# input1.net
KiCad netlist of a schematic drawn in Altium Designer
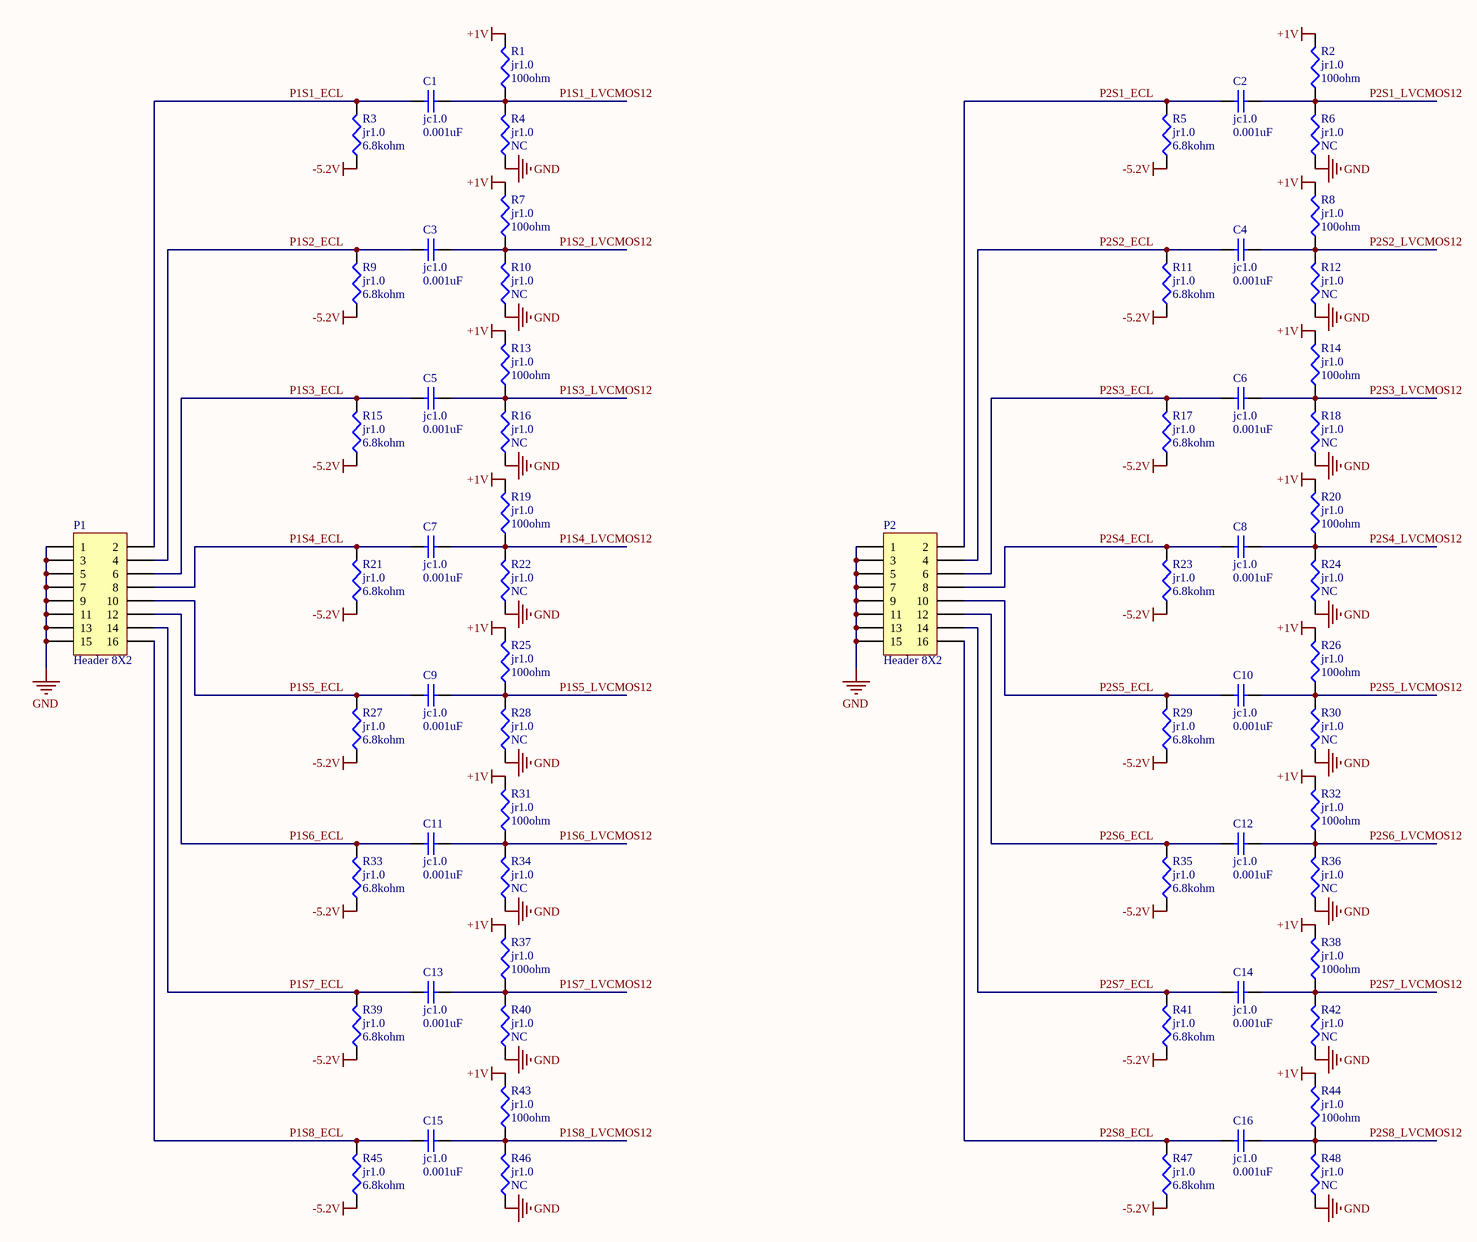
[diagram p0: input1.SchDoc]

(export (version "E")
  (design (tool "Eeschema 10.0.6"))
  (components
    (comp (ref "C1")
      (value "jc1.0")
      (footprint "0402")
      (description "Capacitor")
      (fields (field (name "ALTIUM_VALUE") "0.001uF") (field (name "PUBLISHER") "Altium Limited"))
      (libsource (lib "LIB01DXP2006SchLib") (part "Cap"))
    )
    (comp (ref "C2")
      (value "jc1.0")
      (footprint "0402")
      (description "Capacitor")
      (fields (field (name "ALTIUM_VALUE") "0.001uF") (field (name "PUBLISHER") "Altium Limited"))
      (libsource (lib "LIB01DXP2006SchLib") (part "Cap"))
    )
    (comp (ref "C3")
      (value "jc1.0")
      (footprint "0402")
      (description "Capacitor")
      (fields (field (name "ALTIUM_VALUE") "0.001uF") (field (name "PUBLISHER") "Altium Limited"))
      (libsource (lib "LIB01DXP2006SchLib") (part "Cap"))
    )
    (comp (ref "C4")
      (value "jc1.0")
      (footprint "0402")
      (description "Capacitor")
      (fields (field (name "ALTIUM_VALUE") "0.001uF") (field (name "PUBLISHER") "Altium Limited"))
      (libsource (lib "LIB01DXP2006SchLib") (part "Cap"))
    )
    (comp (ref "C5")
      (value "jc1.0")
      (footprint "0402")
      (description "Capacitor")
      (fields (field (name "ALTIUM_VALUE") "0.001uF") (field (name "PUBLISHER") "Altium Limited"))
      (libsource (lib "LIB01DXP2006SchLib") (part "Cap"))
    )
    (comp (ref "C6")
      (value "jc1.0")
      (footprint "0402")
      (description "Capacitor")
      (fields (field (name "ALTIUM_VALUE") "0.001uF") (field (name "PUBLISHER") "Altium Limited"))
      (libsource (lib "LIB01DXP2006SchLib") (part "Cap"))
    )
    (comp (ref "C7")
      (value "jc1.0")
      (footprint "0402")
      (description "Capacitor")
      (fields (field (name "ALTIUM_VALUE") "0.001uF") (field (name "PUBLISHER") "Altium Limited"))
      (libsource (lib "LIB01DXP2006SchLib") (part "Cap"))
    )
    (comp (ref "C8")
      (value "jc1.0")
      (footprint "0402")
      (description "Capacitor")
      (fields (field (name "ALTIUM_VALUE") "0.001uF") (field (name "PUBLISHER") "Altium Limited"))
      (libsource (lib "LIB01DXP2006SchLib") (part "Cap"))
    )
    (comp (ref "C9")
      (value "jc1.0")
      (footprint "0402")
      (description "Capacitor")
      (fields (field (name "ALTIUM_VALUE") "0.001uF") (field (name "PUBLISHER") "Altium Limited"))
      (libsource (lib "LIB01DXP2006SchLib") (part "Cap"))
    )
    (comp (ref "C10")
      (value "jc1.0")
      (footprint "0402")
      (description "Capacitor")
      (fields (field (name "ALTIUM_VALUE") "0.001uF") (field (name "PUBLISHER") "Altium Limited"))
      (libsource (lib "LIB01DXP2006SchLib") (part "Cap"))
    )
    (comp (ref "C11")
      (value "jc1.0")
      (footprint "0402")
      (description "Capacitor")
      (fields (field (name "ALTIUM_VALUE") "0.001uF") (field (name "PUBLISHER") "Altium Limited"))
      (libsource (lib "LIB01DXP2006SchLib") (part "Cap"))
    )
    (comp (ref "C12")
      (value "jc1.0")
      (footprint "0402")
      (description "Capacitor")
      (fields (field (name "ALTIUM_VALUE") "0.001uF") (field (name "PUBLISHER") "Altium Limited"))
      (libsource (lib "LIB01DXP2006SchLib") (part "Cap"))
    )
    (comp (ref "C13")
      (value "jc1.0")
      (footprint "0402")
      (description "Capacitor")
      (fields (field (name "ALTIUM_VALUE") "0.001uF") (field (name "PUBLISHER") "Altium Limited"))
      (libsource (lib "LIB01DXP2006SchLib") (part "Cap"))
    )
    (comp (ref "C14")
      (value "jc1.0")
      (footprint "0402")
      (description "Capacitor")
      (fields (field (name "ALTIUM_VALUE") "0.001uF") (field (name "PUBLISHER") "Altium Limited"))
      (libsource (lib "LIB01DXP2006SchLib") (part "Cap"))
    )
    (comp (ref "C15")
      (value "jc1.0")
      (footprint "0402")
      (description "Capacitor")
      (fields (field (name "ALTIUM_VALUE") "0.001uF") (field (name "PUBLISHER") "Altium Limited"))
      (libsource (lib "LIB01DXP2006SchLib") (part "Cap"))
    )
    (comp (ref "C16")
      (value "jc1.0")
      (footprint "0402")
      (description "Capacitor")
      (fields (field (name "ALTIUM_VALUE") "0.001uF") (field (name "PUBLISHER") "Altium Limited"))
      (libsource (lib "LIB01DXP2006SchLib") (part "Cap"))
    )
    (comp (ref "P1")
      (value "Header 8X2")
      (footprint "HDR2X8")
      (description "Header, 8-Pin, Dual row")
      (fields (field (name "PUBLISHER") "Altium Limited"))
      (libsource (lib "Miscellaneous Connectors") (part "Header 8X2"))
    )
    (comp (ref "P2")
      (value "Header 8X2")
      (footprint "HDR2X8")
      (description "Header, 8-Pin, Dual row")
      (fields (field (name "PUBLISHER") "Altium Limited"))
      (libsource (lib "Miscellaneous Connectors") (part "Header 8X2"))
    )
    (comp (ref "R1")
      (value "jr1.0")
      (footprint "0402")
      (description "Resistor")
      (fields (field (name "ALTIUM_VALUE") "100ohm") (field (name "PUBLISHER") "Altium Limited"))
      (libsource (lib "LIB01DXP2006SchLib") (part "Res"))
    )
    (comp (ref "R2")
      (value "jr1.0")
      (footprint "0402")
      (description "Resistor")
      (fields (field (name "ALTIUM_VALUE") "100ohm") (field (name "PUBLISHER") "Altium Limited"))
      (libsource (lib "LIB01DXP2006SchLib") (part "Res"))
    )
    (comp (ref "R3")
      (value "jr1.0")
      (footprint "0402")
      (description "Resistor")
      (fields (field (name "ALTIUM_VALUE") "6.8kohm") (field (name "PUBLISHER") "Altium Limited"))
      (libsource (lib "LIB01DXP2006SchLib") (part "Res"))
    )
    (comp (ref "R4")
      (value "jr1.0")
      (footprint "0402")
      (description "Resistor")
      (fields (field (name "ALTIUM_VALUE") "NC") (field (name "PUBLISHER") "Altium Limited"))
      (libsource (lib "LIB01DXP2006SchLib") (part "Res"))
    )
    (comp (ref "R5")
      (value "jr1.0")
      (footprint "0402")
      (description "Resistor")
      (fields (field (name "ALTIUM_VALUE") "6.8kohm") (field (name "PUBLISHER") "Altium Limited"))
      (libsource (lib "LIB01DXP2006SchLib") (part "Res"))
    )
    (comp (ref "R6")
      (value "jr1.0")
      (footprint "0402")
      (description "Resistor")
      (fields (field (name "ALTIUM_VALUE") "NC") (field (name "PUBLISHER") "Altium Limited"))
      (libsource (lib "LIB01DXP2006SchLib") (part "Res"))
    )
    (comp (ref "R7")
      (value "jr1.0")
      (footprint "0402")
      (description "Resistor")
      (fields (field (name "ALTIUM_VALUE") "100ohm") (field (name "PUBLISHER") "Altium Limited"))
      (libsource (lib "LIB01DXP2006SchLib") (part "Res"))
    )
    (comp (ref "R8")
      (value "jr1.0")
      (footprint "0402")
      (description "Resistor")
      (fields (field (name "ALTIUM_VALUE") "100ohm") (field (name "PUBLISHER") "Altium Limited"))
      (libsource (lib "LIB01DXP2006SchLib") (part "Res"))
    )
    (comp (ref "R9")
      (value "jr1.0")
      (footprint "0402")
      (description "Resistor")
      (fields (field (name "ALTIUM_VALUE") "6.8kohm") (field (name "PUBLISHER") "Altium Limited"))
      (libsource (lib "LIB01DXP2006SchLib") (part "Res"))
    )
    (comp (ref "R10")
      (value "jr1.0")
      (footprint "0402")
      (description "Resistor")
      (fields (field (name "ALTIUM_VALUE") "NC") (field (name "PUBLISHER") "Altium Limited"))
      (libsource (lib "LIB01DXP2006SchLib") (part "Res"))
    )
    (comp (ref "R11")
      (value "jr1.0")
      (footprint "0402")
      (description "Resistor")
      (fields (field (name "ALTIUM_VALUE") "6.8kohm") (field (name "PUBLISHER") "Altium Limited"))
      (libsource (lib "LIB01DXP2006SchLib") (part "Res"))
    )
    (comp (ref "R12")
      (value "jr1.0")
      (footprint "0402")
      (description "Resistor")
      (fields (field (name "ALTIUM_VALUE") "NC") (field (name "PUBLISHER") "Altium Limited"))
      (libsource (lib "LIB01DXP2006SchLib") (part "Res"))
    )
    (comp (ref "R13")
      (value "jr1.0")
      (footprint "0402")
      (description "Resistor")
      (fields (field (name "ALTIUM_VALUE") "100ohm") (field (name "PUBLISHER") "Altium Limited"))
      (libsource (lib "LIB01DXP2006SchLib") (part "Res"))
    )
    (comp (ref "R14")
      (value "jr1.0")
      (footprint "0402")
      (description "Resistor")
      (fields (field (name "ALTIUM_VALUE") "100ohm") (field (name "PUBLISHER") "Altium Limited"))
      (libsource (lib "LIB01DXP2006SchLib") (part "Res"))
    )
    (comp (ref "R15")
      (value "jr1.0")
      (footprint "0402")
      (description "Resistor")
      (fields (field (name "ALTIUM_VALUE") "6.8kohm") (field (name "PUBLISHER") "Altium Limited"))
      (libsource (lib "LIB01DXP2006SchLib") (part "Res"))
    )
    (comp (ref "R16")
      (value "jr1.0")
      (footprint "0402")
      (description "Resistor")
      (fields (field (name "ALTIUM_VALUE") "NC") (field (name "PUBLISHER") "Altium Limited"))
      (libsource (lib "LIB01DXP2006SchLib") (part "Res"))
    )
    (comp (ref "R17")
      (value "jr1.0")
      (footprint "0402")
      (description "Resistor")
      (fields (field (name "ALTIUM_VALUE") "6.8kohm") (field (name "PUBLISHER") "Altium Limited"))
      (libsource (lib "LIB01DXP2006SchLib") (part "Res"))
    )
    (comp (ref "R18")
      (value "jr1.0")
      (footprint "0402")
      (description "Resistor")
      (fields (field (name "ALTIUM_VALUE") "NC") (field (name "PUBLISHER") "Altium Limited"))
      (libsource (lib "LIB01DXP2006SchLib") (part "Res"))
    )
    (comp (ref "R19")
      (value "jr1.0")
      (footprint "0402")
      (description "Resistor")
      (fields (field (name "ALTIUM_VALUE") "100ohm") (field (name "PUBLISHER") "Altium Limited"))
      (libsource (lib "LIB01DXP2006SchLib") (part "Res"))
    )
    (comp (ref "R20")
      (value "jr1.0")
      (footprint "0402")
      (description "Resistor")
      (fields (field (name "ALTIUM_VALUE") "100ohm") (field (name "PUBLISHER") "Altium Limited"))
      (libsource (lib "LIB01DXP2006SchLib") (part "Res"))
    )
    (comp (ref "R21")
      (value "jr1.0")
      (footprint "0402")
      (description "Resistor")
      (fields (field (name "ALTIUM_VALUE") "6.8kohm") (field (name "PUBLISHER") "Altium Limited"))
      (libsource (lib "LIB01DXP2006SchLib") (part "Res"))
    )
    (comp (ref "R22")
      (value "jr1.0")
      (footprint "0402")
      (description "Resistor")
      (fields (field (name "ALTIUM_VALUE") "NC") (field (name "PUBLISHER") "Altium Limited"))
      (libsource (lib "LIB01DXP2006SchLib") (part "Res"))
    )
    (comp (ref "R23")
      (value "jr1.0")
      (footprint "0402")
      (description "Resistor")
      (fields (field (name "ALTIUM_VALUE") "6.8kohm") (field (name "PUBLISHER") "Altium Limited"))
      (libsource (lib "LIB01DXP2006SchLib") (part "Res"))
    )
    (comp (ref "R24")
      (value "jr1.0")
      (footprint "0402")
      (description "Resistor")
      (fields (field (name "ALTIUM_VALUE") "NC") (field (name "PUBLISHER") "Altium Limited"))
      (libsource (lib "LIB01DXP2006SchLib") (part "Res"))
    )
    (comp (ref "R25")
      (value "jr1.0")
      (footprint "0402")
      (description "Resistor")
      (fields (field (name "ALTIUM_VALUE") "100ohm") (field (name "PUBLISHER") "Altium Limited"))
      (libsource (lib "LIB01DXP2006SchLib") (part "Res"))
    )
    (comp (ref "R26")
      (value "jr1.0")
      (footprint "0402")
      (description "Resistor")
      (fields (field (name "ALTIUM_VALUE") "100ohm") (field (name "PUBLISHER") "Altium Limited"))
      (libsource (lib "LIB01DXP2006SchLib") (part "Res"))
    )
    (comp (ref "R27")
      (value "jr1.0")
      (footprint "0402")
      (description "Resistor")
      (fields (field (name "ALTIUM_VALUE") "6.8kohm") (field (name "PUBLISHER") "Altium Limited"))
      (libsource (lib "LIB01DXP2006SchLib") (part "Res"))
    )
    (comp (ref "R28")
      (value "jr1.0")
      (footprint "0402")
      (description "Resistor")
      (fields (field (name "ALTIUM_VALUE") "NC") (field (name "PUBLISHER") "Altium Limited"))
      (libsource (lib "LIB01DXP2006SchLib") (part "Res"))
    )
    (comp (ref "R29")
      (value "jr1.0")
      (footprint "0402")
      (description "Resistor")
      (fields (field (name "ALTIUM_VALUE") "6.8kohm") (field (name "PUBLISHER") "Altium Limited"))
      (libsource (lib "LIB01DXP2006SchLib") (part "Res"))
    )
    (comp (ref "R30")
      (value "jr1.0")
      (footprint "0402")
      (description "Resistor")
      (fields (field (name "ALTIUM_VALUE") "NC") (field (name "PUBLISHER") "Altium Limited"))
      (libsource (lib "LIB01DXP2006SchLib") (part "Res"))
    )
    (comp (ref "R31")
      (value "jr1.0")
      (footprint "0402")
      (description "Resistor")
      (fields (field (name "ALTIUM_VALUE") "100ohm") (field (name "PUBLISHER") "Altium Limited"))
      (libsource (lib "LIB01DXP2006SchLib") (part "Res"))
    )
    (comp (ref "R32")
      (value "jr1.0")
      (footprint "0402")
      (description "Resistor")
      (fields (field (name "ALTIUM_VALUE") "100ohm") (field (name "PUBLISHER") "Altium Limited"))
      (libsource (lib "LIB01DXP2006SchLib") (part "Res"))
    )
    (comp (ref "R33")
      (value "jr1.0")
      (footprint "0402")
      (description "Resistor")
      (fields (field (name "ALTIUM_VALUE") "6.8kohm") (field (name "PUBLISHER") "Altium Limited"))
      (libsource (lib "LIB01DXP2006SchLib") (part "Res"))
    )
    (comp (ref "R34")
      (value "jr1.0")
      (footprint "0402")
      (description "Resistor")
      (fields (field (name "ALTIUM_VALUE") "NC") (field (name "PUBLISHER") "Altium Limited"))
      (libsource (lib "LIB01DXP2006SchLib") (part "Res"))
    )
    (comp (ref "R35")
      (value "jr1.0")
      (footprint "0402")
      (description "Resistor")
      (fields (field (name "ALTIUM_VALUE") "6.8kohm") (field (name "PUBLISHER") "Altium Limited"))
      (libsource (lib "LIB01DXP2006SchLib") (part "Res"))
    )
    (comp (ref "R36")
      (value "jr1.0")
      (footprint "0402")
      (description "Resistor")
      (fields (field (name "ALTIUM_VALUE") "NC") (field (name "PUBLISHER") "Altium Limited"))
      (libsource (lib "LIB01DXP2006SchLib") (part "Res"))
    )
    (comp (ref "R37")
      (value "jr1.0")
      (footprint "0402")
      (description "Resistor")
      (fields (field (name "ALTIUM_VALUE") "100ohm") (field (name "PUBLISHER") "Altium Limited"))
      (libsource (lib "LIB01DXP2006SchLib") (part "Res"))
    )
    (comp (ref "R38")
      (value "jr1.0")
      (footprint "0402")
      (description "Resistor")
      (fields (field (name "ALTIUM_VALUE") "100ohm") (field (name "PUBLISHER") "Altium Limited"))
      (libsource (lib "LIB01DXP2006SchLib") (part "Res"))
    )
    (comp (ref "R39")
      (value "jr1.0")
      (footprint "0402")
      (description "Resistor")
      (fields (field (name "ALTIUM_VALUE") "6.8kohm") (field (name "PUBLISHER") "Altium Limited"))
      (libsource (lib "LIB01DXP2006SchLib") (part "Res"))
    )
    (comp (ref "R40")
      (value "jr1.0")
      (footprint "0402")
      (description "Resistor")
      (fields (field (name "ALTIUM_VALUE") "NC") (field (name "PUBLISHER") "Altium Limited"))
      (libsource (lib "LIB01DXP2006SchLib") (part "Res"))
    )
    (comp (ref "R41")
      (value "jr1.0")
      (footprint "0402")
      (description "Resistor")
      (fields (field (name "ALTIUM_VALUE") "6.8kohm") (field (name "PUBLISHER") "Altium Limited"))
      (libsource (lib "LIB01DXP2006SchLib") (part "Res"))
    )
    (comp (ref "R42")
      (value "jr1.0")
      (footprint "0402")
      (description "Resistor")
      (fields (field (name "ALTIUM_VALUE") "NC") (field (name "PUBLISHER") "Altium Limited"))
      (libsource (lib "LIB01DXP2006SchLib") (part "Res"))
    )
    (comp (ref "R43")
      (value "jr1.0")
      (footprint "0402")
      (description "Resistor")
      (fields (field (name "ALTIUM_VALUE") "100ohm") (field (name "PUBLISHER") "Altium Limited"))
      (libsource (lib "LIB01DXP2006SchLib") (part "Res"))
    )
    (comp (ref "R44")
      (value "jr1.0")
      (footprint "0402")
      (description "Resistor")
      (fields (field (name "ALTIUM_VALUE") "100ohm") (field (name "PUBLISHER") "Altium Limited"))
      (libsource (lib "LIB01DXP2006SchLib") (part "Res"))
    )
    (comp (ref "R45")
      (value "jr1.0")
      (footprint "0402")
      (description "Resistor")
      (fields (field (name "ALTIUM_VALUE") "6.8kohm") (field (name "PUBLISHER") "Altium Limited"))
      (libsource (lib "LIB01DXP2006SchLib") (part "Res"))
    )
    (comp (ref "R46")
      (value "jr1.0")
      (footprint "0402")
      (description "Resistor")
      (fields (field (name "ALTIUM_VALUE") "NC") (field (name "PUBLISHER") "Altium Limited"))
      (libsource (lib "LIB01DXP2006SchLib") (part "Res"))
    )
    (comp (ref "R47")
      (value "jr1.0")
      (footprint "0402")
      (description "Resistor")
      (fields (field (name "ALTIUM_VALUE") "6.8kohm") (field (name "PUBLISHER") "Altium Limited"))
      (libsource (lib "LIB01DXP2006SchLib") (part "Res"))
    )
    (comp (ref "R48")
      (value "jr1.0")
      (footprint "0402")
      (description "Resistor")
      (fields (field (name "ALTIUM_VALUE") "NC") (field (name "PUBLISHER") "Altium Limited"))
      (libsource (lib "LIB01DXP2006SchLib") (part "Res"))
    )
  )
  (nets
    (net (code "1") (name "+1V") (class "Default")
      (node (ref "R1") (pin "2") (pinfunction "2_2") (pintype "passive"))
      (node (ref "R13") (pin "2") (pinfunction "2_2") (pintype "passive"))
      (node (ref "R14") (pin "2") (pinfunction "2_2") (pintype "passive"))
      (node (ref "R19") (pin "2") (pinfunction "2_2") (pintype "passive"))
      (node (ref "R2") (pin "2") (pinfunction "2_2") (pintype "passive"))
      (node (ref "R20") (pin "2") (pinfunction "2_2") (pintype "passive"))
      (node (ref "R25") (pin "2") (pinfunction "2_2") (pintype "passive"))
      (node (ref "R26") (pin "2") (pinfunction "2_2") (pintype "passive"))
      (node (ref "R31") (pin "2") (pinfunction "2_2") (pintype "passive"))
      (node (ref "R32") (pin "2") (pinfunction "2_2") (pintype "passive"))
      (node (ref "R37") (pin "2") (pinfunction "2_2") (pintype "passive"))
      (node (ref "R38") (pin "2") (pinfunction "2_2") (pintype "passive"))
      (node (ref "R43") (pin "2") (pinfunction "2_2") (pintype "passive"))
      (node (ref "R44") (pin "2") (pinfunction "2_2") (pintype "passive"))
      (node (ref "R7") (pin "2") (pinfunction "2_2") (pintype "passive"))
      (node (ref "R8") (pin "2") (pinfunction "2_2") (pintype "passive"))
    )
    (net (code "2") (name "-5.2V") (class "Default")
      (node (ref "R11") (pin "1") (pinfunction "1_1") (pintype "passive"))
      (node (ref "R15") (pin "1") (pinfunction "1_1") (pintype "passive"))
      (node (ref "R17") (pin "1") (pinfunction "1_1") (pintype "passive"))
      (node (ref "R21") (pin "1") (pinfunction "1_1") (pintype "passive"))
      (node (ref "R23") (pin "1") (pinfunction "1_1") (pintype "passive"))
      (node (ref "R27") (pin "1") (pinfunction "1_1") (pintype "passive"))
      (node (ref "R29") (pin "1") (pinfunction "1_1") (pintype "passive"))
      (node (ref "R3") (pin "1") (pinfunction "1_1") (pintype "passive"))
      (node (ref "R33") (pin "1") (pinfunction "1_1") (pintype "passive"))
      (node (ref "R35") (pin "1") (pinfunction "1_1") (pintype "passive"))
      (node (ref "R39") (pin "1") (pinfunction "1_1") (pintype "passive"))
      (node (ref "R41") (pin "1") (pinfunction "1_1") (pintype "passive"))
      (node (ref "R45") (pin "1") (pinfunction "1_1") (pintype "passive"))
      (node (ref "R47") (pin "1") (pinfunction "1_1") (pintype "passive"))
      (node (ref "R5") (pin "1") (pinfunction "1_1") (pintype "passive"))
      (node (ref "R9") (pin "1") (pinfunction "1_1") (pintype "passive"))
    )
    (net (code "3") (name "/P1S1_ECL") (class "Default")
      (node (ref "C1") (pin "1") (pinfunction "1_1") (pintype "passive"))
      (node (ref "P1") (pin "2") (pinfunction "2_2") (pintype "passive"))
      (node (ref "R3") (pin "2") (pinfunction "2_2") (pintype "passive"))
    )
    (net (code "4") (name "/P1S1_LVCMOS12") (class "Default")
      (node (ref "C1") (pin "2") (pinfunction "2_2") (pintype "passive"))
      (node (ref "R1") (pin "1") (pinfunction "1_1") (pintype "passive"))
      (node (ref "R4") (pin "2") (pinfunction "2_2") (pintype "passive"))
    )
    (net (code "5") (name "/P1S2_ECL") (class "Default")
      (node (ref "C3") (pin "1") (pinfunction "1_1") (pintype "passive"))
      (node (ref "P1") (pin "4") (pinfunction "4_4") (pintype "passive"))
      (node (ref "R9") (pin "2") (pinfunction "2_2") (pintype "passive"))
    )
    (net (code "6") (name "/P1S2_LVCMOS12") (class "Default")
      (node (ref "C3") (pin "2") (pinfunction "2_2") (pintype "passive"))
      (node (ref "R10") (pin "2") (pinfunction "2_2") (pintype "passive"))
      (node (ref "R7") (pin "1") (pinfunction "1_1") (pintype "passive"))
    )
    (net (code "7") (name "/P1S3_ECL") (class "Default")
      (node (ref "C5") (pin "1") (pinfunction "1_1") (pintype "passive"))
      (node (ref "P1") (pin "6") (pinfunction "6_6") (pintype "passive"))
      (node (ref "R15") (pin "2") (pinfunction "2_2") (pintype "passive"))
    )
    (net (code "8") (name "/P1S3_LVCMOS12") (class "Default")
      (node (ref "C5") (pin "2") (pinfunction "2_2") (pintype "passive"))
      (node (ref "R13") (pin "1") (pinfunction "1_1") (pintype "passive"))
      (node (ref "R16") (pin "2") (pinfunction "2_2") (pintype "passive"))
    )
    (net (code "9") (name "/P1S4_ECL") (class "Default")
      (node (ref "C7") (pin "1") (pinfunction "1_1") (pintype "passive"))
      (node (ref "P1") (pin "8") (pinfunction "8_8") (pintype "passive"))
      (node (ref "R21") (pin "2") (pinfunction "2_2") (pintype "passive"))
    )
    (net (code "10") (name "/P1S4_LVCMOS12") (class "Default")
      (node (ref "C7") (pin "2") (pinfunction "2_2") (pintype "passive"))
      (node (ref "R19") (pin "1") (pinfunction "1_1") (pintype "passive"))
      (node (ref "R22") (pin "2") (pinfunction "2_2") (pintype "passive"))
    )
    (net (code "11") (name "/P1S5_ECL") (class "Default")
      (node (ref "C9") (pin "1") (pinfunction "1_1") (pintype "passive"))
      (node (ref "P1") (pin "10") (pinfunction "10_10") (pintype "passive"))
      (node (ref "R27") (pin "2") (pinfunction "2_2") (pintype "passive"))
    )
    (net (code "12") (name "/P1S5_LVCMOS12") (class "Default")
      (node (ref "C9") (pin "2") (pinfunction "2_2") (pintype "passive"))
      (node (ref "R25") (pin "1") (pinfunction "1_1") (pintype "passive"))
      (node (ref "R28") (pin "2") (pinfunction "2_2") (pintype "passive"))
    )
    (net (code "13") (name "/P1S6_ECL") (class "Default")
      (node (ref "C11") (pin "1") (pinfunction "1_1") (pintype "passive"))
      (node (ref "P1") (pin "12") (pinfunction "12_12") (pintype "passive"))
      (node (ref "R33") (pin "2") (pinfunction "2_2") (pintype "passive"))
    )
    (net (code "14") (name "/P1S6_LVCMOS12") (class "Default")
      (node (ref "C11") (pin "2") (pinfunction "2_2") (pintype "passive"))
      (node (ref "R31") (pin "1") (pinfunction "1_1") (pintype "passive"))
      (node (ref "R34") (pin "2") (pinfunction "2_2") (pintype "passive"))
    )
    (net (code "15") (name "/P1S7_ECL") (class "Default")
      (node (ref "C13") (pin "1") (pinfunction "1_1") (pintype "passive"))
      (node (ref "P1") (pin "14") (pinfunction "14_14") (pintype "passive"))
      (node (ref "R39") (pin "2") (pinfunction "2_2") (pintype "passive"))
    )
    (net (code "16") (name "/P1S7_LVCMOS12") (class "Default")
      (node (ref "C13") (pin "2") (pinfunction "2_2") (pintype "passive"))
      (node (ref "R37") (pin "1") (pinfunction "1_1") (pintype "passive"))
      (node (ref "R40") (pin "2") (pinfunction "2_2") (pintype "passive"))
    )
    (net (code "17") (name "/P1S8_ECL") (class "Default")
      (node (ref "C15") (pin "1") (pinfunction "1_1") (pintype "passive"))
      (node (ref "P1") (pin "16") (pinfunction "16_16") (pintype "passive"))
      (node (ref "R45") (pin "2") (pinfunction "2_2") (pintype "passive"))
    )
    (net (code "18") (name "/P1S8_LVCMOS12") (class "Default")
      (node (ref "C15") (pin "2") (pinfunction "2_2") (pintype "passive"))
      (node (ref "R43") (pin "1") (pinfunction "1_1") (pintype "passive"))
      (node (ref "R46") (pin "2") (pinfunction "2_2") (pintype "passive"))
    )
    (net (code "19") (name "/P2S1_ECL") (class "Default")
      (node (ref "C2") (pin "1") (pinfunction "1_1") (pintype "passive"))
      (node (ref "P2") (pin "2") (pinfunction "2_2") (pintype "passive"))
      (node (ref "R5") (pin "2") (pinfunction "2_2") (pintype "passive"))
    )
    (net (code "20") (name "/P2S1_LVCMOS12") (class "Default")
      (node (ref "C2") (pin "2") (pinfunction "2_2") (pintype "passive"))
      (node (ref "R2") (pin "1") (pinfunction "1_1") (pintype "passive"))
      (node (ref "R6") (pin "2") (pinfunction "2_2") (pintype "passive"))
    )
    (net (code "21") (name "/P2S2_ECL") (class "Default")
      (node (ref "C4") (pin "1") (pinfunction "1_1") (pintype "passive"))
      (node (ref "P2") (pin "4") (pinfunction "4_4") (pintype "passive"))
      (node (ref "R11") (pin "2") (pinfunction "2_2") (pintype "passive"))
    )
    (net (code "22") (name "/P2S2_LVCMOS12") (class "Default")
      (node (ref "C4") (pin "2") (pinfunction "2_2") (pintype "passive"))
      (node (ref "R12") (pin "2") (pinfunction "2_2") (pintype "passive"))
      (node (ref "R8") (pin "1") (pinfunction "1_1") (pintype "passive"))
    )
    (net (code "23") (name "/P2S3_ECL") (class "Default")
      (node (ref "C6") (pin "1") (pinfunction "1_1") (pintype "passive"))
      (node (ref "P2") (pin "6") (pinfunction "6_6") (pintype "passive"))
      (node (ref "R17") (pin "2") (pinfunction "2_2") (pintype "passive"))
    )
    (net (code "24") (name "/P2S3_LVCMOS12") (class "Default")
      (node (ref "C6") (pin "2") (pinfunction "2_2") (pintype "passive"))
      (node (ref "R14") (pin "1") (pinfunction "1_1") (pintype "passive"))
      (node (ref "R18") (pin "2") (pinfunction "2_2") (pintype "passive"))
    )
    (net (code "25") (name "/P2S4_ECL") (class "Default")
      (node (ref "C8") (pin "1") (pinfunction "1_1") (pintype "passive"))
      (node (ref "P2") (pin "8") (pinfunction "8_8") (pintype "passive"))
      (node (ref "R23") (pin "2") (pinfunction "2_2") (pintype "passive"))
    )
    (net (code "26") (name "/P2S4_LVCMOS12") (class "Default")
      (node (ref "C8") (pin "2") (pinfunction "2_2") (pintype "passive"))
      (node (ref "R20") (pin "1") (pinfunction "1_1") (pintype "passive"))
      (node (ref "R24") (pin "2") (pinfunction "2_2") (pintype "passive"))
    )
    (net (code "27") (name "/P2S5_ECL") (class "Default")
      (node (ref "C10") (pin "1") (pinfunction "1_1") (pintype "passive"))
      (node (ref "P2") (pin "10") (pinfunction "10_10") (pintype "passive"))
      (node (ref "R29") (pin "2") (pinfunction "2_2") (pintype "passive"))
    )
    (net (code "28") (name "/P2S5_LVCMOS12") (class "Default")
      (node (ref "C10") (pin "2") (pinfunction "2_2") (pintype "passive"))
      (node (ref "R26") (pin "1") (pinfunction "1_1") (pintype "passive"))
      (node (ref "R30") (pin "2") (pinfunction "2_2") (pintype "passive"))
    )
    (net (code "29") (name "/P2S6_ECL") (class "Default")
      (node (ref "C12") (pin "1") (pinfunction "1_1") (pintype "passive"))
      (node (ref "P2") (pin "12") (pinfunction "12_12") (pintype "passive"))
      (node (ref "R35") (pin "2") (pinfunction "2_2") (pintype "passive"))
    )
    (net (code "30") (name "/P2S6_LVCMOS12") (class "Default")
      (node (ref "C12") (pin "2") (pinfunction "2_2") (pintype "passive"))
      (node (ref "R32") (pin "1") (pinfunction "1_1") (pintype "passive"))
      (node (ref "R36") (pin "2") (pinfunction "2_2") (pintype "passive"))
    )
    (net (code "31") (name "/P2S7_ECL") (class "Default")
      (node (ref "C14") (pin "1") (pinfunction "1_1") (pintype "passive"))
      (node (ref "P2") (pin "14") (pinfunction "14_14") (pintype "passive"))
      (node (ref "R41") (pin "2") (pinfunction "2_2") (pintype "passive"))
    )
    (net (code "32") (name "/P2S7_LVCMOS12") (class "Default")
      (node (ref "C14") (pin "2") (pinfunction "2_2") (pintype "passive"))
      (node (ref "R38") (pin "1") (pinfunction "1_1") (pintype "passive"))
      (node (ref "R42") (pin "2") (pinfunction "2_2") (pintype "passive"))
    )
    (net (code "33") (name "/P2S8_ECL") (class "Default")
      (node (ref "C16") (pin "1") (pinfunction "1_1") (pintype "passive"))
      (node (ref "P2") (pin "16") (pinfunction "16_16") (pintype "passive"))
      (node (ref "R47") (pin "2") (pinfunction "2_2") (pintype "passive"))
    )
    (net (code "34") (name "/P2S8_LVCMOS12") (class "Default")
      (node (ref "C16") (pin "2") (pinfunction "2_2") (pintype "passive"))
      (node (ref "R44") (pin "1") (pinfunction "1_1") (pintype "passive"))
      (node (ref "R48") (pin "2") (pinfunction "2_2") (pintype "passive"))
    )
    (net (code "35") (name "GND") (class "Default")
      (node (ref "P1") (pin "1") (pinfunction "1_1") (pintype "passive"))
      (node (ref "P1") (pin "11") (pinfunction "11_11") (pintype "passive"))
      (node (ref "P1") (pin "13") (pinfunction "13_13") (pintype "passive"))
      (node (ref "P1") (pin "15") (pinfunction "15_15") (pintype "passive"))
      (node (ref "P1") (pin "3") (pinfunction "3_3") (pintype "passive"))
      (node (ref "P1") (pin "5") (pinfunction "5_5") (pintype "passive"))
      (node (ref "P1") (pin "7") (pinfunction "7_7") (pintype "passive"))
      (node (ref "P1") (pin "9") (pinfunction "9_9") (pintype "passive"))
      (node (ref "P2") (pin "1") (pinfunction "1_1") (pintype "passive"))
      (node (ref "P2") (pin "11") (pinfunction "11_11") (pintype "passive"))
      (node (ref "P2") (pin "13") (pinfunction "13_13") (pintype "passive"))
      (node (ref "P2") (pin "15") (pinfunction "15_15") (pintype "passive"))
      (node (ref "P2") (pin "3") (pinfunction "3_3") (pintype "passive"))
      (node (ref "P2") (pin "5") (pinfunction "5_5") (pintype "passive"))
      (node (ref "P2") (pin "7") (pinfunction "7_7") (pintype "passive"))
      (node (ref "P2") (pin "9") (pinfunction "9_9") (pintype "passive"))
      (node (ref "R10") (pin "1") (pinfunction "1_1") (pintype "passive"))
      (node (ref "R12") (pin "1") (pinfunction "1_1") (pintype "passive"))
      (node (ref "R16") (pin "1") (pinfunction "1_1") (pintype "passive"))
      (node (ref "R18") (pin "1") (pinfunction "1_1") (pintype "passive"))
      (node (ref "R22") (pin "1") (pinfunction "1_1") (pintype "passive"))
      (node (ref "R24") (pin "1") (pinfunction "1_1") (pintype "passive"))
      (node (ref "R28") (pin "1") (pinfunction "1_1") (pintype "passive"))
      (node (ref "R30") (pin "1") (pinfunction "1_1") (pintype "passive"))
      (node (ref "R34") (pin "1") (pinfunction "1_1") (pintype "passive"))
      (node (ref "R36") (pin "1") (pinfunction "1_1") (pintype "passive"))
      (node (ref "R4") (pin "1") (pinfunction "1_1") (pintype "passive"))
      (node (ref "R40") (pin "1") (pinfunction "1_1") (pintype "passive"))
      (node (ref "R42") (pin "1") (pinfunction "1_1") (pintype "passive"))
      (node (ref "R46") (pin "1") (pinfunction "1_1") (pintype "passive"))
      (node (ref "R48") (pin "1") (pinfunction "1_1") (pintype "passive"))
      (node (ref "R6") (pin "1") (pinfunction "1_1") (pintype "passive"))
    )
  )
)
